# Simple-Fet_-v015-pro-mini.net
KiCad netlist of a schematic drawn in EAGLE
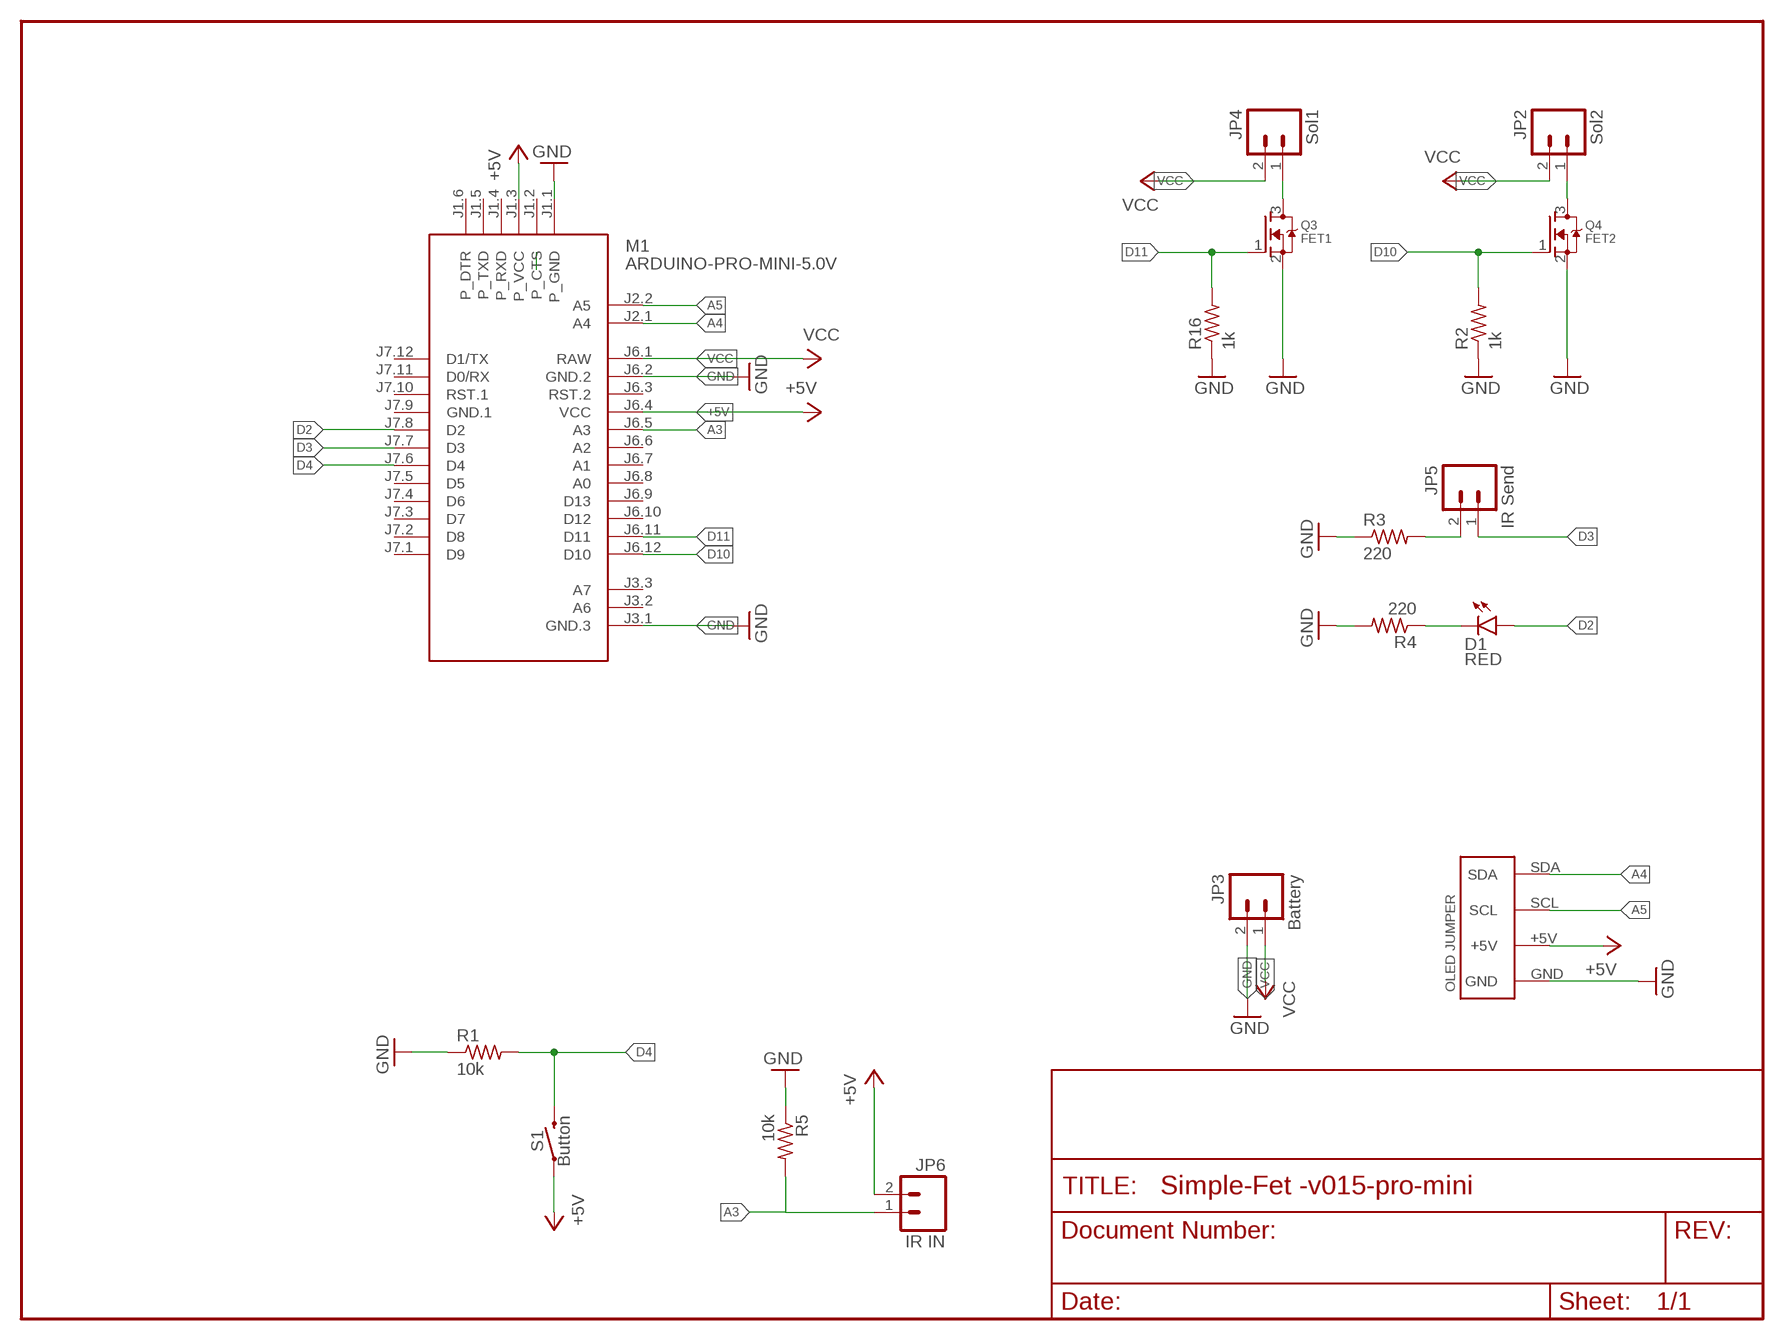
[diagram p0: schematic, sheet 1]

(export (version "E")
  (design (tool "Eeschema 10.0.6"))
  (components
    (comp (ref "D1")
      (value "RED")
      (footprint "eagle-import:LED-1206")
      (fields (field (name "MPN") "HSMC-C150"))
      (libsource (lib "eagle-import") (part "LED-RED1206"))
    )
    (comp (ref "JP2")
      (value "Sol2")
      (footprint "eagle-import:1X02")
      (fields (field (name "MF") "MOLEX") (field (name "MPN") "22-23-2021"))
      (libsource (lib "eagle-import") (part "M02PTH"))
    )
    (comp (ref "JP3")
      (value "Battery")
      (footprint "eagle-import:1X02")
      (fields (field (name "MF") "KEYSTONE ELECTR") (field (name "MPN") "2239"))
      (libsource (lib "eagle-import") (part "M02PTH"))
    )
    (comp (ref "JP4")
      (value "Sol1")
      (footprint "eagle-import:1X02")
      (fields (field (name "MF") "MOLEX") (field (name "MPN") "22-23-2021"))
      (libsource (lib "eagle-import") (part "M02PTH"))
    )
    (comp (ref "JP5")
      (value "IR Send")
      (footprint "eagle-import:1X02")
      (fields (field (name "MF") "FAIRCHILD SEMICONDUCTOR") (field (name "MPN") "QEE122"))
      (libsource (lib "eagle-import") (part "M02PTH"))
    )
    (comp (ref "JP6")
      (value "IR IN")
      (footprint "eagle-import:1X02")
      (fields (field (name "MF") "FAIRCHILD SEMICONDUCTOR") (field (name "MPN") "QEE113"))
      (libsource (lib "eagle-import") (part "M02PTH"))
    )
    (comp (ref "M1")
      (value "ARDUINO-PRO-MINI-5.0V")
      (footprint "eagle-import:ARDUINO-PRO-MINI")
      (libsource (lib "eagle-import") (part "ARDUINO-PRO-MINI-5.0V"))
    )
    (comp (ref "Q3")
      (value "FET1")
      (footprint "eagle-import:SOT23")
      (fields (field (name "MPN") "SI2392ADS-T1-GE3"))
      (libsource (lib "eagle-import") (part "MOSFET-NREFLOW"))
    )
    (comp (ref "Q4")
      (value "FET2")
      (footprint "eagle-import:SOT23")
      (fields (field (name "MPN") "SI2392ADS-T1-GE3"))
      (libsource (lib "eagle-import") (part "MOSFET-NREFLOW"))
    )
    (comp (ref "R1")
      (value "10k")
      (footprint "eagle-import:M1206")
      (fields (field (name "MPN") "MC1206S4F1002T5E"))
      (libsource (lib "eagle-import") (part "R-US_M1206"))
    )
    (comp (ref "R2")
      (value "1k")
      (footprint "eagle-import:M1206")
      (fields (field (name "MPN") "RT1206FRE071KL"))
      (libsource (lib "eagle-import") (part "R-US_M1206"))
    )
    (comp (ref "R3")
      (value "220")
      (footprint "eagle-import:M1206")
      (fields (field (name "MF") "BOURNS, INC.") (field (name "MPN") "CR1206FX2200ELF"))
      (libsource (lib "eagle-import") (part "R-US_M1206"))
    )
    (comp (ref "R4")
      (value "220")
      (footprint "eagle-import:M1206")
      (fields (field (name "MF") "BOURNS, INC.") (field (name "MPN") "CR1206FX2200ELF"))
      (libsource (lib "eagle-import") (part "R-US_M1206"))
    )
    (comp (ref "R5")
      (value "10k")
      (footprint "eagle-import:M1206")
      (fields (field (name "MPN") "MC1206S4F1002T5E"))
      (libsource (lib "eagle-import") (part "R-US_M1206"))
    )
    (comp (ref "R16")
      (value "1k")
      (footprint "eagle-import:M1206")
      (fields (field (name "MPN") "RT1206FRE071KL"))
      (libsource (lib "eagle-import") (part "R-US_M1206"))
    )
    (comp (ref "S1")
      (value "Button")
      (footprint "eagle-import:TACTILE_SWITCH_SMD_6.0X3.5MM")
      (libsource (lib "eagle-import") (part "MOMENTARY-SWITCH-SPST-SMD-6.0X3.5MM"))
    )
    (comp (ref "U$2")
      (value "OLEDHEADER")
      (footprint "eagle-import:OLED-CON")
      (libsource (lib "eagle-import") (part "OLEDHEADER"))
    )
  )
  (nets
    (net (code "1") (name "+5V") (class "Default")
      (node (ref "JP6") (pin "2") (pinfunction "2_2") (pintype "passive"))
      (node (ref "M1") (pin "J1.3") (pinfunction "P_VCC_J1.3") (pintype "bidirectional"))
      (node (ref "M1") (pin "J6.4") (pinfunction "VCC_J6.4") (pintype "power_in"))
      (node (ref "S1") (pin "1") (pinfunction "1_1") (pintype "passive"))
      (node (ref "U$2") (pin "+5V") (pinfunction "+5V_+5V") (pintype "bidirectional"))
    )
    (net (code "2") (name "/GND.1") (class "Default")
      (node (ref "M1") (pin "J7.9") (pinfunction "GND.1_J7.9") (pintype "power_in"))
    )
    (net (code "3") (name "A3") (class "Default")
      (node (ref "JP6") (pin "1") (pinfunction "1_1") (pintype "passive"))
      (node (ref "M1") (pin "J6.5") (pinfunction "A3_J6.5") (pintype "bidirectional"))
      (node (ref "R5") (pin "2") (pinfunction "2_2") (pintype "passive"))
    )
    (net (code "4") (name "A4") (class "Default")
      (node (ref "M1") (pin "J2.1") (pinfunction "A4_J2.1") (pintype "bidirectional"))
      (node (ref "U$2") (pin "SDA") (pinfunction "SDA_SDA") (pintype "bidirectional"))
    )
    (net (code "5") (name "A5") (class "Default")
      (node (ref "M1") (pin "J2.2") (pinfunction "A5_J2.2") (pintype "bidirectional"))
      (node (ref "U$2") (pin "SCL") (pinfunction "SCL_SCL") (pintype "bidirectional"))
    )
    (net (code "6") (name "D2") (class "Default")
      (node (ref "D1") (pin "A") (pinfunction "A_A") (pintype "passive"))
      (node (ref "M1") (pin "J7.8") (pinfunction "D2_J7.8") (pintype "bidirectional"))
    )
    (net (code "7") (name "D3") (class "Default")
      (node (ref "JP5") (pin "1") (pinfunction "1_1") (pintype "passive"))
      (node (ref "M1") (pin "J7.7") (pinfunction "D3_J7.7") (pintype "bidirectional"))
    )
    (net (code "8") (name "D4") (class "Default")
      (node (ref "M1") (pin "J7.6") (pinfunction "D4_J7.6") (pintype "bidirectional"))
      (node (ref "R1") (pin "2") (pinfunction "2_2") (pintype "passive"))
      (node (ref "S1") (pin "2") (pinfunction "2_2") (pintype "passive"))
    )
    (net (code "9") (name "D10") (class "Default")
      (node (ref "M1") (pin "J6.12") (pinfunction "D10_J6.12") (pintype "bidirectional"))
      (node (ref "Q4") (pin "1") (pinfunction "G_1") (pintype "bidirectional"))
      (node (ref "R2") (pin "2") (pinfunction "2_2") (pintype "passive"))
    )
    (net (code "10") (name "D11") (class "Default")
      (node (ref "M1") (pin "J6.11") (pinfunction "D11_J6.11") (pintype "bidirectional"))
      (node (ref "Q3") (pin "1") (pinfunction "G_1") (pintype "bidirectional"))
      (node (ref "R16") (pin "2") (pinfunction "2_2") (pintype "passive"))
    )
    (net (code "11") (name "GND") (class "Default")
      (node (ref "JP3") (pin "2") (pinfunction "2_2") (pintype "passive"))
      (node (ref "M1") (pin "J1.1") (pinfunction "P_GND_J1.1") (pintype "bidirectional"))
      (node (ref "M1") (pin "J3.1") (pinfunction "GND.3_J3.1") (pintype "bidirectional"))
      (node (ref "M1") (pin "J6.2") (pinfunction "GND.2_J6.2") (pintype "power_in"))
      (node (ref "Q3") (pin "2") (pinfunction "S_2") (pintype "bidirectional"))
      (node (ref "Q4") (pin "2") (pinfunction "S_2") (pintype "bidirectional"))
      (node (ref "R1") (pin "1") (pinfunction "1_1") (pintype "passive"))
      (node (ref "R16") (pin "1") (pinfunction "1_1") (pintype "passive"))
      (node (ref "R2") (pin "1") (pinfunction "1_1") (pintype "passive"))
      (node (ref "R3") (pin "1") (pinfunction "1_1") (pintype "passive"))
      (node (ref "R4") (pin "2") (pinfunction "2_2") (pintype "passive"))
      (node (ref "R5") (pin "1") (pinfunction "1_1") (pintype "passive"))
      (node (ref "U$2") (pin "GND") (pinfunction "GND_GND") (pintype "bidirectional"))
    )
    (net (code "12") (name "Net-(D1-PadC)") (class "Default")
      (node (ref "D1") (pin "C") (pinfunction "C_C") (pintype "passive"))
      (node (ref "R4") (pin "1") (pinfunction "1_1") (pintype "passive"))
    )
    (net (code "13") (name "Net-(JP5-Pad2)") (class "Default")
      (node (ref "JP5") (pin "2") (pinfunction "2_2") (pintype "passive"))
      (node (ref "R3") (pin "2") (pinfunction "2_2") (pintype "passive"))
    )
    (net (code "14") (name "Net-(Q3-D)") (class "Default")
      (node (ref "JP4") (pin "1") (pinfunction "1_1") (pintype "passive"))
      (node (ref "Q3") (pin "3") (pinfunction "D_3") (pintype "bidirectional"))
    )
    (net (code "15") (name "Net-(Q4-D)") (class "Default")
      (node (ref "JP2") (pin "1") (pinfunction "1_1") (pintype "passive"))
      (node (ref "Q4") (pin "3") (pinfunction "D_3") (pintype "bidirectional"))
    )
    (net (code "16") (name "VCC") (class "Default")
      (node (ref "JP2") (pin "2") (pinfunction "2_2") (pintype "passive"))
      (node (ref "JP3") (pin "1") (pinfunction "1_1") (pintype "passive"))
      (node (ref "JP4") (pin "2") (pinfunction "2_2") (pintype "passive"))
      (node (ref "M1") (pin "J6.1") (pinfunction "RAW_J6.1") (pintype "power_in"))
    )
    (net (code "17") (name "unconnected-(M1-A0-PadJ6.8)") (class "Default")
      (node (ref "M1") (pin "J6.8") (pinfunction "A0_J6.8") (pintype "bidirectional"))
    )
    (net (code "18") (name "unconnected-(M1-A1-PadJ6.7)") (class "Default")
      (node (ref "M1") (pin "J6.7") (pinfunction "A1_J6.7") (pintype "bidirectional"))
    )
    (net (code "19") (name "unconnected-(M1-A2-PadJ6.6)") (class "Default")
      (node (ref "M1") (pin "J6.6") (pinfunction "A2_J6.6") (pintype "bidirectional"))
    )
    (net (code "20") (name "unconnected-(M1-A6-PadJ3.2)") (class "Default")
      (node (ref "M1") (pin "J3.2") (pinfunction "A6_J3.2") (pintype "bidirectional"))
    )
    (net (code "21") (name "unconnected-(M1-A7-PadJ3.3)") (class "Default")
      (node (ref "M1") (pin "J3.3") (pinfunction "A7_J3.3") (pintype "bidirectional"))
    )
    (net (code "22") (name "unconnected-(M1-D0{slash}RX-PadJ7.11)") (class "Default")
      (node (ref "M1") (pin "J7.11") (pinfunction "D0/RX_J7.11") (pintype "bidirectional"))
    )
    (net (code "23") (name "unconnected-(M1-D1{slash}TX-PadJ7.12)") (class "Default")
      (node (ref "M1") (pin "J7.12") (pinfunction "D1/TX_J7.12") (pintype "bidirectional"))
    )
    (net (code "24") (name "unconnected-(M1-D5-PadJ7.5)") (class "Default")
      (node (ref "M1") (pin "J7.5") (pinfunction "D5_J7.5") (pintype "bidirectional"))
    )
    (net (code "25") (name "unconnected-(M1-D6-PadJ7.4)") (class "Default")
      (node (ref "M1") (pin "J7.4") (pinfunction "D6_J7.4") (pintype "bidirectional"))
    )
    (net (code "26") (name "unconnected-(M1-D7-PadJ7.3)") (class "Default")
      (node (ref "M1") (pin "J7.3") (pinfunction "D7_J7.3") (pintype "bidirectional"))
    )
    (net (code "27") (name "unconnected-(M1-D8-PadJ7.2)") (class "Default")
      (node (ref "M1") (pin "J7.2") (pinfunction "D8_J7.2") (pintype "bidirectional"))
    )
    (net (code "28") (name "unconnected-(M1-D9-PadJ7.1)") (class "Default")
      (node (ref "M1") (pin "J7.1") (pinfunction "D9_J7.1") (pintype "bidirectional"))
    )
    (net (code "29") (name "unconnected-(M1-D12-PadJ6.10)") (class "Default")
      (node (ref "M1") (pin "J6.10") (pinfunction "D12_J6.10") (pintype "bidirectional"))
    )
    (net (code "30") (name "unconnected-(M1-D13-PadJ6.9)") (class "Default")
      (node (ref "M1") (pin "J6.9") (pinfunction "D13_J6.9") (pintype "bidirectional"))
    )
    (net (code "31") (name "unconnected-(M1-P_CTS-PadJ1.2)") (class "Default")
      (node (ref "M1") (pin "J1.2") (pinfunction "P_CTS_J1.2") (pintype "bidirectional"))
    )
    (net (code "32") (name "unconnected-(M1-P_DTR-PadJ1.6)") (class "Default")
      (node (ref "M1") (pin "J1.6") (pinfunction "P_DTR_J1.6") (pintype "bidirectional"))
    )
    (net (code "33") (name "unconnected-(M1-P_RXD-PadJ1.4)") (class "Default")
      (node (ref "M1") (pin "J1.4") (pinfunction "P_RXD_J1.4") (pintype "bidirectional"))
    )
    (net (code "34") (name "unconnected-(M1-P_TXD-PadJ1.5)") (class "Default")
      (node (ref "M1") (pin "J1.5") (pinfunction "P_TXD_J1.5") (pintype "bidirectional"))
    )
    (net (code "35") (name "unconnected-(M1-RST.1-PadJ7.10)") (class "Default")
      (node (ref "M1") (pin "J7.10") (pinfunction "RST.1_J7.10") (pintype "bidirectional"))
    )
    (net (code "36") (name "unconnected-(M1-RST.2-PadJ6.3)") (class "Default")
      (node (ref "M1") (pin "J6.3") (pinfunction "RST.2_J6.3") (pintype "bidirectional"))
    )
  )
)
